# piezo-preamp-alex-rice-FETS_v2.net
KiCad netlist of a schematic drawn in EAGLE
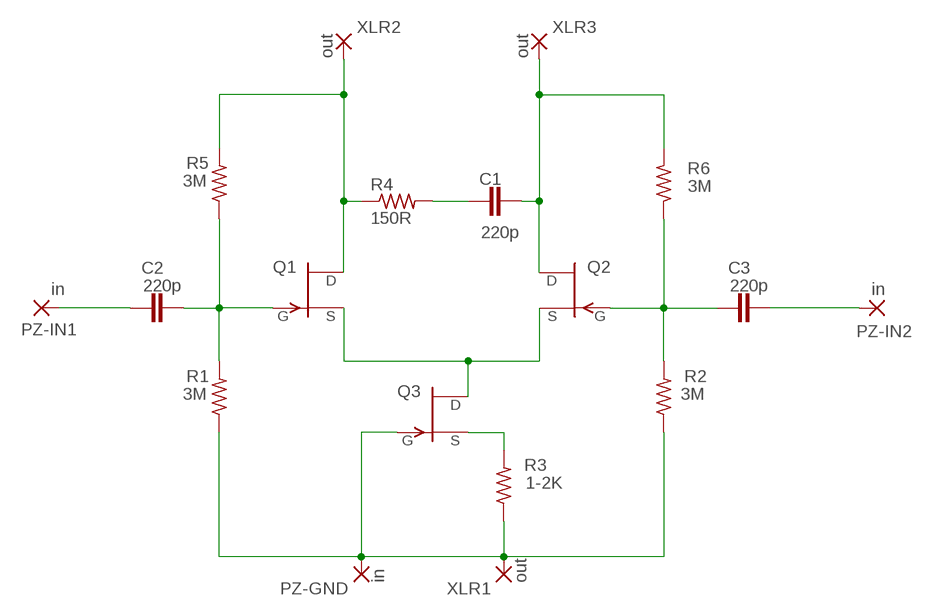
[diagram p0: schematic, sheet 1]

(export (version "E")
  (design (tool "Eeschema 10.0.6"))
  (components
    (comp (ref "C1")
      (value "220p")
      (footprint "eagle-import:C050-030X075")
      (libsource (lib "eagle-import") (part "C-EU050-030X075"))
    )
    (comp (ref "C2")
      (value "220p")
      (footprint "eagle-import:C050-030X075")
      (libsource (lib "eagle-import") (part "C-EU050-030X075"))
    )
    (comp (ref "C3")
      (value "220p")
      (footprint "eagle-import:C050-030X075")
      (libsource (lib "eagle-import") (part "C-EU050-030X075"))
    )
    (comp (ref "PZ-GND")
      (value "in")
      (footprint "eagle-import:3,81_1,1")
      (libsource (lib "eagle-import") (part "3,81/1,1"))
    )
    (comp (ref "PZ-IN1")
      (value "in")
      (footprint "eagle-import:3,81_1,1")
      (libsource (lib "eagle-import") (part "3,81/1,1"))
    )
    (comp (ref "PZ-IN2")
      (value "in")
      (footprint "eagle-import:3,81_1,1")
      (libsource (lib "eagle-import") (part "3,81/1,1"))
    )
    (comp (ref "Q1")
      (value "2N3819")
      (footprint "eagle-import:TO92")
      (libsource (lib "eagle-import") (part "2N3819-WIDETO92_WIDE"))
    )
    (comp (ref "Q2")
      (value "2N3819-WIDETO92_WIDE")
      (footprint "eagle-import:TO92")
      (libsource (lib "eagle-import") (part "2N3819-WIDETO92_WIDE"))
    )
    (comp (ref "Q3")
      (value "2N3819-WIDETO92_WIDE")
      (footprint "eagle-import:TO92")
      (libsource (lib "eagle-import") (part "2N3819-WIDETO92_WIDE"))
    )
    (comp (ref "R1")
      (value "3M")
      (footprint "eagle-import:0414V")
      (libsource (lib "eagle-import") (part "R-US_0414/5V"))
    )
    (comp (ref "R2")
      (value "3M")
      (footprint "eagle-import:0414V")
      (libsource (lib "eagle-import") (part "R-US_0414/5V"))
    )
    (comp (ref "R3")
      (value "1-2K")
      (footprint "eagle-import:0414V")
      (libsource (lib "eagle-import") (part "R-US_0414/5V"))
    )
    (comp (ref "R4")
      (value "150R")
      (footprint "eagle-import:0414V")
      (libsource (lib "eagle-import") (part "resistor_R-US_0414/5V"))
    )
    (comp (ref "R5")
      (value "3M")
      (footprint "eagle-import:0414V")
      (libsource (lib "eagle-import") (part "R-US_0414/5V"))
    )
    (comp (ref "R6")
      (value "3M")
      (footprint "eagle-import:0414V")
      (libsource (lib "eagle-import") (part "R-US_0414/5V"))
    )
    (comp (ref "XLR1")
      (value "out")
      (footprint "eagle-import:3,81_1,1")
      (libsource (lib "eagle-import") (part "3,81/1,1"))
    )
    (comp (ref "XLR2")
      (value "out")
      (footprint "eagle-import:3,81_1,1")
      (libsource (lib "eagle-import") (part "3,81/1,1"))
    )
    (comp (ref "XLR3")
      (value "out")
      (footprint "eagle-import:3,81_1,1")
      (libsource (lib "eagle-import") (part "3,81/1,1"))
    )
  )
  (nets
    (net (code "1") (name "Net-(C1-Pad1)") (class "Default")
      (node (ref "C1") (pin "1") (pinfunction "1_1") (pintype "passive"))
      (node (ref "R4") (pin "2") (pinfunction "2_2") (pintype "passive"))
    )
    (net (code "2") (name "Net-(PZ-GND-P)") (class "Default")
      (node (ref "PZ-GND") (pin "1") (pinfunction "P_1") (pintype "passive"))
      (node (ref "Q3") (pin "2") (pinfunction "G_2") (pintype "passive"))
      (node (ref "R1") (pin "1") (pinfunction "1_1") (pintype "passive"))
      (node (ref "R2") (pin "1") (pinfunction "1_1") (pintype "passive"))
      (node (ref "R3") (pin "1") (pinfunction "1_1") (pintype "passive"))
      (node (ref "XLR1") (pin "1") (pinfunction "P_1") (pintype "passive"))
    )
    (net (code "3") (name "Net-(PZ-IN1-P)") (class "Default")
      (node (ref "C2") (pin "1") (pinfunction "1_1") (pintype "passive"))
      (node (ref "PZ-IN1") (pin "1") (pinfunction "P_1") (pintype "passive"))
    )
    (net (code "4") (name "Net-(PZ-IN2-P)") (class "Default")
      (node (ref "C3") (pin "2") (pinfunction "2_2") (pintype "passive"))
      (node (ref "PZ-IN2") (pin "1") (pinfunction "P_1") (pintype "passive"))
    )
    (net (code "5") (name "Net-(Q1-D)") (class "Default")
      (node (ref "Q1") (pin "1") (pinfunction "D_1") (pintype "passive"))
      (node (ref "R4") (pin "1") (pinfunction "1_1") (pintype "passive"))
      (node (ref "R5") (pin "2") (pinfunction "2_2") (pintype "passive"))
      (node (ref "XLR2") (pin "1") (pinfunction "P_1") (pintype "passive"))
    )
    (net (code "6") (name "Net-(Q1-G)") (class "Default")
      (node (ref "C2") (pin "2") (pinfunction "2_2") (pintype "passive"))
      (node (ref "Q1") (pin "2") (pinfunction "G_2") (pintype "passive"))
      (node (ref "R1") (pin "2") (pinfunction "2_2") (pintype "passive"))
      (node (ref "R5") (pin "1") (pinfunction "1_1") (pintype "passive"))
    )
    (net (code "7") (name "Net-(Q1-S)") (class "Default")
      (node (ref "Q1") (pin "3") (pinfunction "S_3") (pintype "passive"))
      (node (ref "Q2") (pin "3") (pinfunction "S_3") (pintype "passive"))
      (node (ref "Q3") (pin "1") (pinfunction "D_1") (pintype "passive"))
    )
    (net (code "8") (name "Net-(Q2-D)") (class "Default")
      (node (ref "C1") (pin "2") (pinfunction "2_2") (pintype "passive"))
      (node (ref "Q2") (pin "1") (pinfunction "D_1") (pintype "passive"))
      (node (ref "R6") (pin "2") (pinfunction "2_2") (pintype "passive"))
      (node (ref "XLR3") (pin "1") (pinfunction "P_1") (pintype "passive"))
    )
    (net (code "9") (name "Net-(Q2-G)") (class "Default")
      (node (ref "C3") (pin "1") (pinfunction "1_1") (pintype "passive"))
      (node (ref "Q2") (pin "2") (pinfunction "G_2") (pintype "passive"))
      (node (ref "R2") (pin "2") (pinfunction "2_2") (pintype "passive"))
      (node (ref "R6") (pin "1") (pinfunction "1_1") (pintype "passive"))
    )
    (net (code "10") (name "Net-(Q3-S)") (class "Default")
      (node (ref "Q3") (pin "3") (pinfunction "S_3") (pintype "passive"))
      (node (ref "R3") (pin "2") (pinfunction "2_2") (pintype "passive"))
    )
  )
)
